# Omni-BASIC-BOTTOM.net
KiCad netlist of a schematic drawn in EAGLE
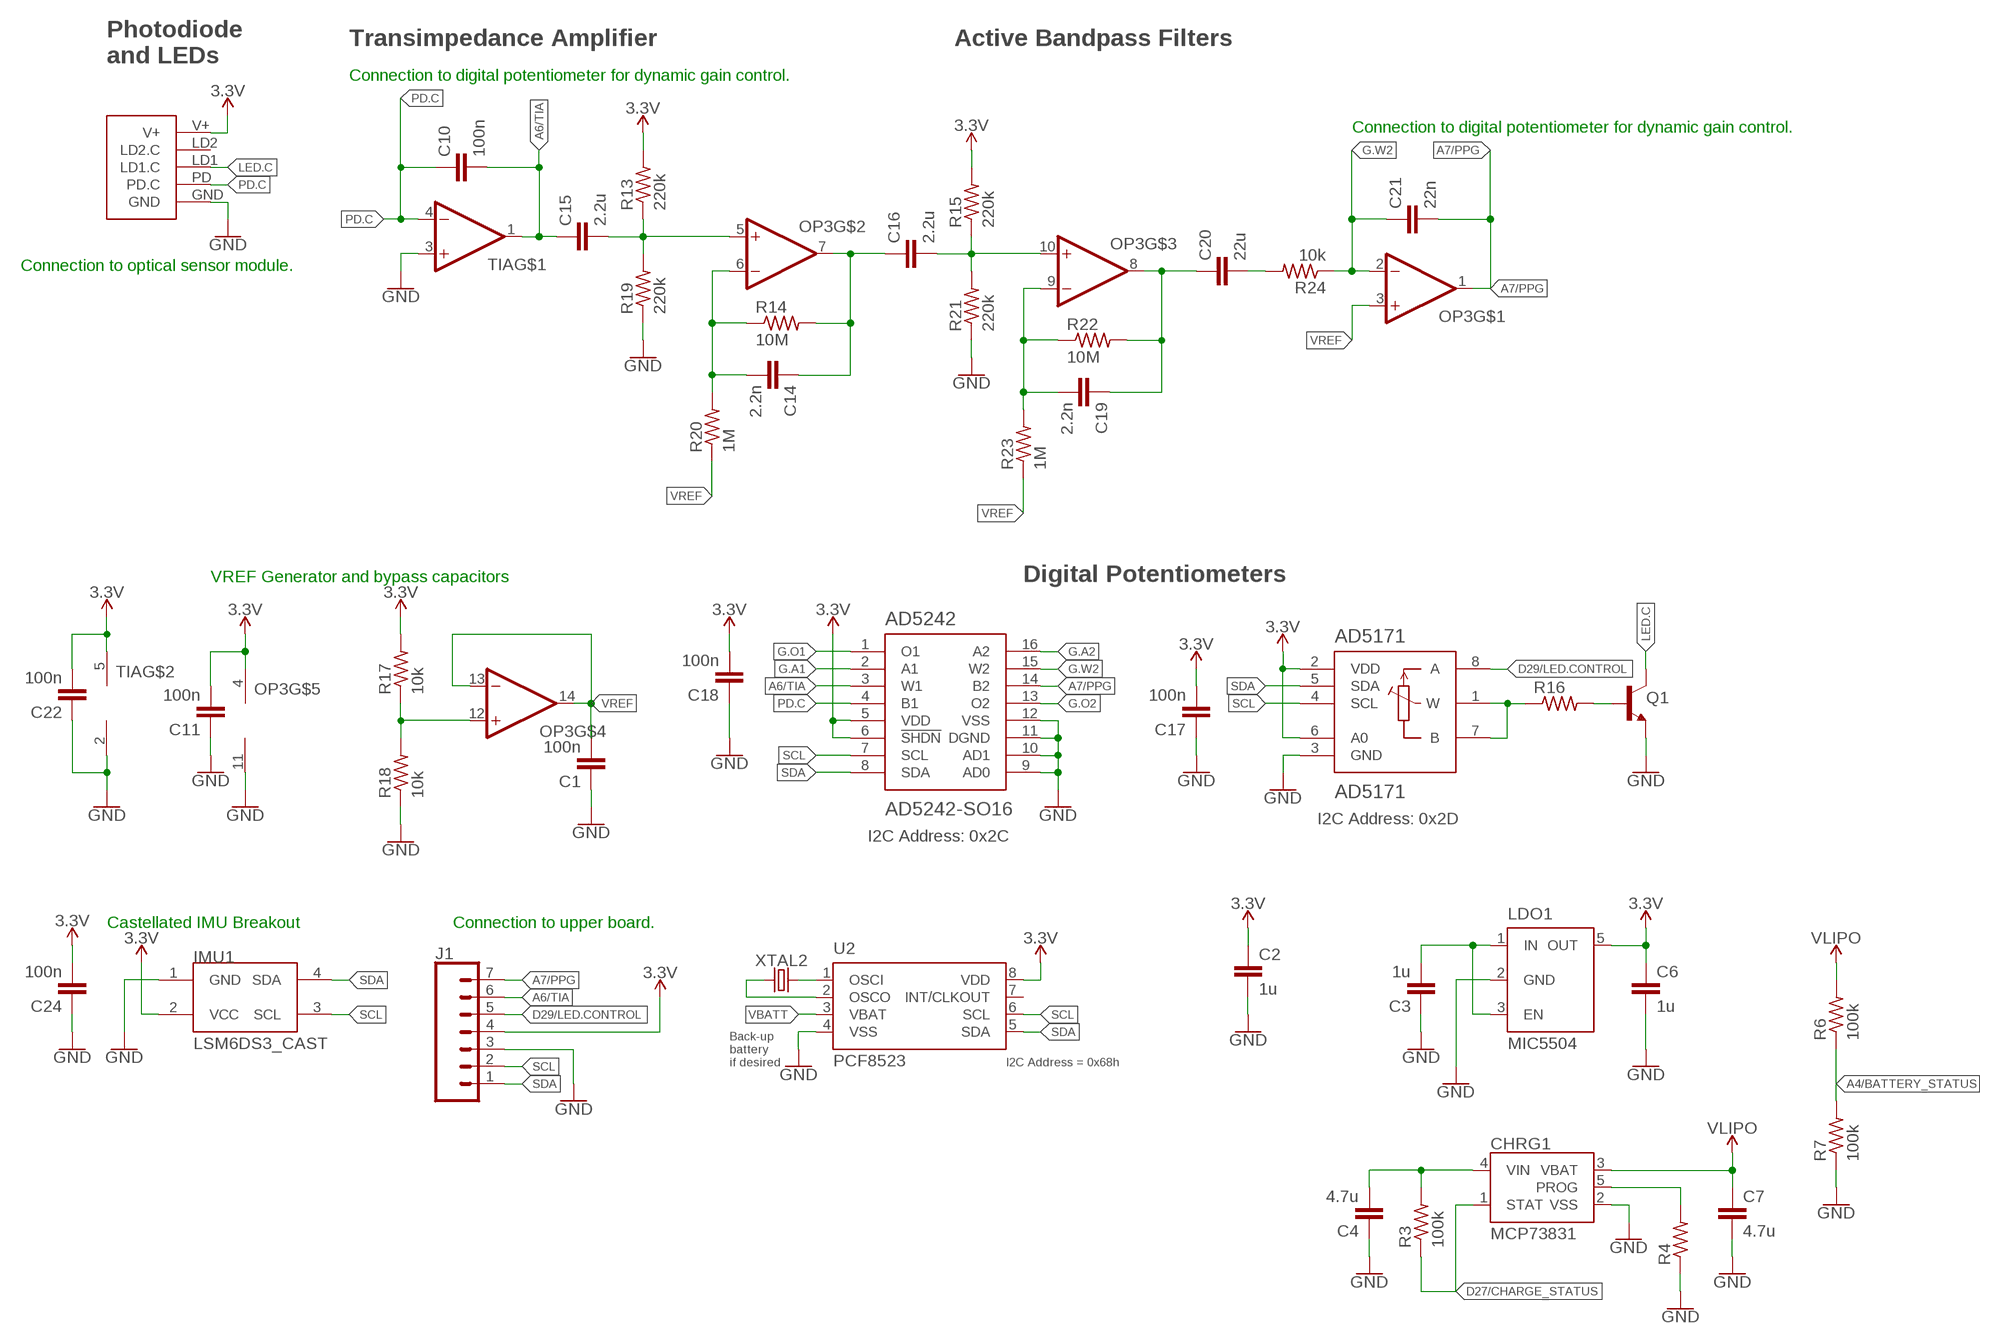
[diagram p0: schematic, sheet 1]

(export (version "E")
  (design (tool "Eeschema 10.0.6"))
  (components
    (comp (ref "AD5171")
      (value "AD5171")
      (footprint "eagle-import:SOT-23-8")
      (libsource (lib "eagle-import") (part "AD5171"))
    )
    (comp (ref "AD5242")
      (value "AD5242-SO16")
      (footprint "eagle-import:SO16")
      (libsource (lib "eagle-import") (part "AD5242-SO16"))
    )
    (comp (ref "C1")
      (value "100n")
      (footprint "eagle-import:C0603")
      (libsource (lib "eagle-import") (part "CAPACITOR0603"))
    )
    (comp (ref "C2")
      (value "1u")
      (footprint "eagle-import:C0603")
      (libsource (lib "eagle-import") (part "CAPACITOR0603"))
    )
    (comp (ref "C3")
      (value "1u")
      (footprint "eagle-import:C0603")
      (libsource (lib "eagle-import") (part "CAPACITOR0603"))
    )
    (comp (ref "C4")
      (value "4.7u")
      (footprint "eagle-import:C0603")
      (libsource (lib "eagle-import") (part "CAPACITOR0603"))
    )
    (comp (ref "C6")
      (value "1u")
      (footprint "eagle-import:C0603")
      (libsource (lib "eagle-import") (part "CAPACITOR0603"))
    )
    (comp (ref "C7")
      (value "4.7u")
      (footprint "eagle-import:C0603")
      (libsource (lib "eagle-import") (part "CAPACITOR0603"))
    )
    (comp (ref "C10")
      (value "100n")
      (footprint "eagle-import:C0603")
      (libsource (lib "eagle-import") (part "CAPACITOR0603"))
    )
    (comp (ref "C11")
      (value "100n")
      (footprint "eagle-import:C0603")
      (libsource (lib "eagle-import") (part "CAPACITOR0603"))
    )
    (comp (ref "C14")
      (value "2.2n")
      (footprint "eagle-import:C0603")
      (libsource (lib "eagle-import") (part "CAPACITOR0603"))
    )
    (comp (ref "C15")
      (value "2.2u")
      (footprint "eagle-import:C0603")
      (libsource (lib "eagle-import") (part "CAPACITOR0603"))
    )
    (comp (ref "C16")
      (value "2.2u")
      (footprint "eagle-import:C0603")
      (libsource (lib "eagle-import") (part "CAPACITOR0603"))
    )
    (comp (ref "C17")
      (value "100n")
      (footprint "eagle-import:C0603")
      (libsource (lib "eagle-import") (part "CAPACITOR0603"))
    )
    (comp (ref "C18")
      (value "100n")
      (footprint "eagle-import:C0603")
      (libsource (lib "eagle-import") (part "CAPACITOR0603"))
    )
    (comp (ref "C19")
      (value "2.2n")
      (footprint "eagle-import:C0603")
      (libsource (lib "eagle-import") (part "CAPACITOR0603"))
    )
    (comp (ref "C20")
      (value "22u")
      (footprint "eagle-import:C0603")
      (libsource (lib "eagle-import") (part "CAPACITOR0603"))
    )
    (comp (ref "C21")
      (value "22n")
      (footprint "eagle-import:C0603")
      (libsource (lib "eagle-import") (part "CAPACITOR0603"))
    )
    (comp (ref "C22")
      (value "100n")
      (footprint "eagle-import:C0603")
      (libsource (lib "eagle-import") (part "CAPACITOR0603"))
    )
    (comp (ref "C24")
      (value "100n")
      (footprint "eagle-import:C0603")
      (libsource (lib "eagle-import") (part "CAPACITOR0603"))
    )
    (comp (ref "CHRG1")
      (value "MCP73831")
      (footprint "eagle-import:SOT23-5")
      (libsource (lib "eagle-import") (part "MCP73831"))
    )
    (comp (ref "IMU1")
      (value "LSM6DS3_CAST")
      (footprint "eagle-import:LSM6DS3_CAST")
      (libsource (lib "eagle-import") (part "LSM6DS3_CAST"))
    )
    (comp (ref "J1")
      (value "CONN_07-1.27MM")
      (footprint "eagle-import:1X07_1.27MM")
      (libsource (lib "eagle-import") (part "CONN_07-1.27MM"))
    )
    (comp (ref "LDO1")
      (value "MIC5504")
      (footprint "eagle-import:SOT23-5")
      (libsource (lib "eagle-import") (part "MIC5504"))
    )
    (comp (ref "OP3")
      (value "OP-QUAD-SO14")
      (footprint "eagle-import:SO14")
      (libsource (lib "eagle-import") (part "OP-QUAD-SO14"))
    )
    (comp (ref "Q1")
      (value "NPN-GENERIC")
      (footprint "eagle-import:SOT23-3")
      (libsource (lib "eagle-import") (part "NPN-GENERIC"))
    )
    (comp (ref "R3")
      (value "100k")
      (footprint "eagle-import:R0603")
      (libsource (lib "eagle-import") (part "RESISTOR0603"))
    )
    (comp (ref "R4")
      (value "RESISTOR0603")
      (footprint "eagle-import:R0603")
      (libsource (lib "eagle-import") (part "RESISTOR0603"))
    )
    (comp (ref "R6")
      (value "100k")
      (footprint "eagle-import:R0603")
      (libsource (lib "eagle-import") (part "RESISTOR0603"))
    )
    (comp (ref "R7")
      (value "100k")
      (footprint "eagle-import:R0603")
      (libsource (lib "eagle-import") (part "RESISTOR0603"))
    )
    (comp (ref "R13")
      (value "220k")
      (footprint "eagle-import:R0603")
      (libsource (lib "eagle-import") (part "RESISTOR0603"))
    )
    (comp (ref "R14")
      (value "10M")
      (footprint "eagle-import:R0603")
      (libsource (lib "eagle-import") (part "RESISTOR0603"))
    )
    (comp (ref "R15")
      (value "220k")
      (footprint "eagle-import:R0603")
      (libsource (lib "eagle-import") (part "RESISTOR0603"))
    )
    (comp (ref "R16")
      (value "RESISTOR0603")
      (footprint "eagle-import:R0603")
      (libsource (lib "eagle-import") (part "RESISTOR0603"))
    )
    (comp (ref "R17")
      (value "10k")
      (footprint "eagle-import:R0402")
      (libsource (lib "eagle-import") (part "RESISTOR0402"))
    )
    (comp (ref "R18")
      (value "10k")
      (footprint "eagle-import:R0402")
      (libsource (lib "eagle-import") (part "RESISTOR0402"))
    )
    (comp (ref "R19")
      (value "220k")
      (footprint "eagle-import:R0603")
      (libsource (lib "eagle-import") (part "RESISTOR0603"))
    )
    (comp (ref "R20")
      (value "1M")
      (footprint "eagle-import:R0603")
      (libsource (lib "eagle-import") (part "RESISTOR0603"))
    )
    (comp (ref "R21")
      (value "220k")
      (footprint "eagle-import:R0603")
      (libsource (lib "eagle-import") (part "RESISTOR0603"))
    )
    (comp (ref "R22")
      (value "10M")
      (footprint "eagle-import:R0603")
      (libsource (lib "eagle-import") (part "RESISTOR0603"))
    )
    (comp (ref "R23")
      (value "1M")
      (footprint "eagle-import:R0603")
      (libsource (lib "eagle-import") (part "RESISTOR0603"))
    )
    (comp (ref "R24")
      (value "10k")
      (footprint "eagle-import:R0603")
      (libsource (lib "eagle-import") (part "RESISTOR0603"))
    )
    (comp (ref "TIA")
      (value "OP-SINGLEOT")
      (footprint "eagle-import:SOT23-5")
      (libsource (lib "eagle-import") (part "OP-SINGLEOT"))
    )
    (comp (ref "U$3")
      (value "PPG.MODULE.2")
      (footprint "eagle-import:PPG.MODULE.2")
      (libsource (lib "eagle-import") (part "PPG.MODULE.2"))
    )
    (comp (ref "U2")
      (value "PCF8523")
      (footprint "eagle-import:SO8")
      (libsource (lib "eagle-import") (part "PCF8523"))
    )
    (comp (ref "XTAL2")
      (value "32.7680kHz")
      (footprint "eagle-import:2-SMD.NOLEAD.2.0MMTO1.2MM")
      (fields (field (name "FREQ") "32.7680KHZ"))
      (libsource (lib "eagle-import") (part "CRYSTALECS-.327-12.5-12-C-TR"))
    )
  )
  (nets
    (net (code "1") (name "3.3V") (class "Default")
      (node (ref "AD5171") (pin "2") (pinfunction "VDD_2") (pintype "bidirectional"))
      (node (ref "AD5171") (pin "6") (pinfunction "A0_6") (pintype "bidirectional"))
      (node (ref "AD5242") (pin "5") (pinfunction "VDD_5") (pintype "bidirectional"))
      (node (ref "AD5242") (pin "6") (pinfunction "~{SHDN}_6") (pintype "bidirectional"))
      (node (ref "C11") (pin "2") (pinfunction "2_2") (pintype "passive"))
      (node (ref "C17") (pin "2") (pinfunction "2_2") (pintype "passive"))
      (node (ref "C18") (pin "2") (pinfunction "2_2") (pintype "passive"))
      (node (ref "C2") (pin "1") (pinfunction "1_1") (pintype "passive"))
      (node (ref "C22") (pin "2") (pinfunction "2_2") (pintype "passive"))
      (node (ref "C24") (pin "2") (pinfunction "2_2") (pintype "passive"))
      (node (ref "C6") (pin "1") (pinfunction "1_1") (pintype "passive"))
      (node (ref "IMU1") (pin "2") (pinfunction "VCC_2") (pintype "bidirectional"))
      (node (ref "J1") (pin "4") (pinfunction "4_4") (pintype "passive"))
      (node (ref "LDO1") (pin "5") (pinfunction "OUT_5") (pintype "bidirectional"))
      (node (ref "OP3") (pin "4") (pinfunction "V+_4") (pintype "power_in"))
      (node (ref "R13") (pin "2") (pinfunction "2_2") (pintype "passive"))
      (node (ref "R15") (pin "2") (pinfunction "2_2") (pintype "passive"))
      (node (ref "R17") (pin "2") (pinfunction "2_2") (pintype "passive"))
      (node (ref "TIA") (pin "5") (pinfunction "V+_5") (pintype "power_in"))
      (node (ref "U$3") (pin "V+") (pinfunction "V+_V+") (pintype "bidirectional"))
      (node (ref "U2") (pin "8") (pinfunction "VDD_8") (pintype "power_in"))
    )
    (net (code "2") (name "A4{slash}BATTERY_STATUS") (class "Default")
      (node (ref "R6") (pin "1") (pinfunction "1_1") (pintype "passive"))
      (node (ref "R7") (pin "2") (pinfunction "2_2") (pintype "passive"))
    )
    (net (code "3") (name "A6{slash}TIA") (class "Default")
      (node (ref "AD5242") (pin "3") (pinfunction "W1_3") (pintype "bidirectional"))
      (node (ref "C10") (pin "2") (pinfunction "2_2") (pintype "passive"))
      (node (ref "C15") (pin "1") (pinfunction "1_1") (pintype "passive"))
      (node (ref "J1") (pin "6") (pinfunction "6_6") (pintype "passive"))
      (node (ref "TIA") (pin "1") (pinfunction "OUT_1") (pintype "output"))
    )
    (net (code "4") (name "A7{slash}PPG") (class "Default")
      (node (ref "AD5242") (pin "14") (pinfunction "B2_14") (pintype "bidirectional"))
      (node (ref "C21") (pin "2") (pinfunction "2_2") (pintype "passive"))
      (node (ref "J1") (pin "7") (pinfunction "7_7") (pintype "passive"))
      (node (ref "OP3") (pin "1") (pinfunction "OUT_1") (pintype "output"))
    )
    (net (code "5") (name "D27{slash}CHARGE_STATUS") (class "Default")
      (node (ref "CHRG1") (pin "1") (pinfunction "STAT_1") (pintype "output"))
      (node (ref "R3") (pin "1") (pinfunction "1_1") (pintype "passive"))
    )
    (net (code "6") (name "D29{slash}LED.CONTROL") (class "Default")
      (node (ref "AD5171") (pin "8") (pinfunction "A_8") (pintype "bidirectional"))
      (node (ref "J1") (pin "5") (pinfunction "5_5") (pintype "passive"))
    )
    (net (code "7") (name "G.A1") (class "Default")
      (node (ref "AD5242") (pin "2") (pinfunction "A1_2") (pintype "bidirectional"))
    )
    (net (code "8") (name "G.A2") (class "Default")
      (node (ref "AD5242") (pin "16") (pinfunction "A2_16") (pintype "bidirectional"))
    )
    (net (code "9") (name "G.O1") (class "Default")
      (node (ref "AD5242") (pin "1") (pinfunction "O1_1") (pintype "bidirectional"))
    )
    (net (code "10") (name "G.O2") (class "Default")
      (node (ref "AD5242") (pin "13") (pinfunction "O2_13") (pintype "bidirectional"))
    )
    (net (code "11") (name "G.W2") (class "Default")
      (node (ref "AD5242") (pin "15") (pinfunction "W2_15") (pintype "bidirectional"))
      (node (ref "C21") (pin "1") (pinfunction "1_1") (pintype "passive"))
      (node (ref "OP3") (pin "2") (pinfunction "-IN_2") (pintype "input"))
      (node (ref "R24") (pin "1") (pinfunction "1_1") (pintype "passive"))
    )
    (net (code "12") (name "GND") (class "Default")
      (node (ref "AD5171") (pin "3") (pinfunction "GND_3") (pintype "bidirectional"))
      (node (ref "AD5242") (pin "10") (pinfunction "AD1_10") (pintype "bidirectional"))
      (node (ref "AD5242") (pin "11") (pinfunction "DGND_11") (pintype "bidirectional"))
      (node (ref "AD5242") (pin "12") (pinfunction "VSS_12") (pintype "bidirectional"))
      (node (ref "AD5242") (pin "9") (pinfunction "AD0_9") (pintype "bidirectional"))
      (node (ref "C1") (pin "1") (pinfunction "1_1") (pintype "passive"))
      (node (ref "C11") (pin "1") (pinfunction "1_1") (pintype "passive"))
      (node (ref "C17") (pin "1") (pinfunction "1_1") (pintype "passive"))
      (node (ref "C18") (pin "1") (pinfunction "1_1") (pintype "passive"))
      (node (ref "C2") (pin "2") (pinfunction "2_2") (pintype "passive"))
      (node (ref "C22") (pin "1") (pinfunction "1_1") (pintype "passive"))
      (node (ref "C24") (pin "1") (pinfunction "1_1") (pintype "passive"))
      (node (ref "C3") (pin "1") (pinfunction "1_1") (pintype "passive"))
      (node (ref "C4") (pin "1") (pinfunction "1_1") (pintype "passive"))
      (node (ref "C6") (pin "2") (pinfunction "2_2") (pintype "passive"))
      (node (ref "C7") (pin "2") (pinfunction "2_2") (pintype "passive"))
      (node (ref "CHRG1") (pin "2") (pinfunction "VSS_2") (pintype "power_in"))
      (node (ref "IMU1") (pin "1") (pinfunction "GND_1") (pintype "bidirectional"))
      (node (ref "J1") (pin "3") (pinfunction "3_3") (pintype "passive"))
      (node (ref "LDO1") (pin "2") (pinfunction "GND_2") (pintype "bidirectional"))
      (node (ref "OP3") (pin "11") (pinfunction "V-_11") (pintype "power_in"))
      (node (ref "Q1") (pin "2") (pinfunction "E_2") (pintype "passive"))
      (node (ref "R18") (pin "1") (pinfunction "1_1") (pintype "passive"))
      (node (ref "R19") (pin "1") (pinfunction "1_1") (pintype "passive"))
      (node (ref "R21") (pin "1") (pinfunction "1_1") (pintype "passive"))
      (node (ref "R4") (pin "1") (pinfunction "1_1") (pintype "passive"))
      (node (ref "R7") (pin "1") (pinfunction "1_1") (pintype "passive"))
      (node (ref "TIA") (pin "2") (pinfunction "V-_2") (pintype "power_in"))
      (node (ref "TIA") (pin "3") (pinfunction "+IN_3") (pintype "input"))
      (node (ref "U$3") (pin "GND") (pinfunction "GND_GND") (pintype "bidirectional"))
      (node (ref "U2") (pin "4") (pinfunction "VSS_4") (pintype "power_in"))
    )
    (net (code "13") (name "LED.C") (class "Default")
      (node (ref "Q1") (pin "3") (pinfunction "C_3") (pintype "passive"))
      (node (ref "U$3") (pin "LD1") (pinfunction "LD1.C_LD1") (pintype "bidirectional"))
    )
    (net (code "14") (name "Net-(AD5171-B)") (class "Default")
      (node (ref "AD5171") (pin "1") (pinfunction "W_1") (pintype "bidirectional"))
      (node (ref "AD5171") (pin "7") (pinfunction "B_7") (pintype "bidirectional"))
      (node (ref "R16") (pin "1") (pinfunction "1_1") (pintype "passive"))
    )
    (net (code "15") (name "Net-(C20-Pad2)") (class "Default")
      (node (ref "C20") (pin "2") (pinfunction "2_2") (pintype "passive"))
      (node (ref "R24") (pin "2") (pinfunction "2_2") (pintype "passive"))
    )
    (net (code "16") (name "Net-(CHRG1-PROG)") (class "Default")
      (node (ref "CHRG1") (pin "5") (pinfunction "PROG_5") (pintype "input"))
      (node (ref "R4") (pin "2") (pinfunction "2_2") (pintype "passive"))
    )
    (net (code "17") (name "Net-(CHRG1-VIN)") (class "Default")
      (node (ref "C4") (pin "2") (pinfunction "2_2") (pintype "passive"))
      (node (ref "CHRG1") (pin "4") (pinfunction "VIN_4") (pintype "power_in"))
      (node (ref "R3") (pin "2") (pinfunction "2_2") (pintype "passive"))
    )
    (net (code "18") (name "Net-(LDO1-EN)") (class "Default")
      (node (ref "C3") (pin "2") (pinfunction "2_2") (pintype "passive"))
      (node (ref "LDO1") (pin "1") (pinfunction "IN_1") (pintype "bidirectional"))
      (node (ref "LDO1") (pin "3") (pinfunction "EN_3") (pintype "bidirectional"))
    )
    (net (code "19") (name "Net-(OP3B-+IN)") (class "Default")
      (node (ref "C15") (pin "2") (pinfunction "2_2") (pintype "passive"))
      (node (ref "OP3") (pin "5") (pinfunction "+IN_5") (pintype "input"))
      (node (ref "R13") (pin "1") (pinfunction "1_1") (pintype "passive"))
      (node (ref "R19") (pin "2") (pinfunction "2_2") (pintype "passive"))
    )
    (net (code "20") (name "Net-(OP3B--IN)") (class "Default")
      (node (ref "C14") (pin "2") (pinfunction "2_2") (pintype "passive"))
      (node (ref "OP3") (pin "6") (pinfunction "-IN_6") (pintype "input"))
      (node (ref "R14") (pin "1") (pinfunction "1_1") (pintype "passive"))
      (node (ref "R20") (pin "2") (pinfunction "2_2") (pintype "passive"))
    )
    (net (code "21") (name "Net-(OP3B-OUT)") (class "Default")
      (node (ref "C14") (pin "1") (pinfunction "1_1") (pintype "passive"))
      (node (ref "C16") (pin "1") (pinfunction "1_1") (pintype "passive"))
      (node (ref "OP3") (pin "7") (pinfunction "OUT_7") (pintype "output"))
      (node (ref "R14") (pin "2") (pinfunction "2_2") (pintype "passive"))
    )
    (net (code "22") (name "Net-(OP3C-+IN)") (class "Default")
      (node (ref "C16") (pin "2") (pinfunction "2_2") (pintype "passive"))
      (node (ref "OP3") (pin "10") (pinfunction "+IN_10") (pintype "input"))
      (node (ref "R15") (pin "1") (pinfunction "1_1") (pintype "passive"))
      (node (ref "R21") (pin "2") (pinfunction "2_2") (pintype "passive"))
    )
    (net (code "23") (name "Net-(OP3C--IN)") (class "Default")
      (node (ref "C19") (pin "2") (pinfunction "2_2") (pintype "passive"))
      (node (ref "OP3") (pin "9") (pinfunction "-IN_9") (pintype "input"))
      (node (ref "R22") (pin "1") (pinfunction "1_1") (pintype "passive"))
      (node (ref "R23") (pin "2") (pinfunction "2_2") (pintype "passive"))
    )
    (net (code "24") (name "Net-(OP3C-OUT)") (class "Default")
      (node (ref "C19") (pin "1") (pinfunction "1_1") (pintype "passive"))
      (node (ref "C20") (pin "1") (pinfunction "1_1") (pintype "passive"))
      (node (ref "OP3") (pin "8") (pinfunction "OUT_8") (pintype "output"))
      (node (ref "R22") (pin "2") (pinfunction "2_2") (pintype "passive"))
    )
    (net (code "25") (name "Net-(OP3D-+IN)") (class "Default")
      (node (ref "OP3") (pin "12") (pinfunction "+IN_12") (pintype "input"))
      (node (ref "R17") (pin "1") (pinfunction "1_1") (pintype "passive"))
      (node (ref "R18") (pin "2") (pinfunction "2_2") (pintype "passive"))
    )
    (net (code "26") (name "Net-(Q1-B)") (class "Default")
      (node (ref "Q1") (pin "1") (pinfunction "B_1") (pintype "passive"))
      (node (ref "R16") (pin "2") (pinfunction "2_2") (pintype "passive"))
    )
    (net (code "27") (name "Net-(U2-OSCI)") (class "Default")
      (node (ref "U2") (pin "1") (pinfunction "OSCI_1") (pintype "bidirectional"))
      (node (ref "XTAL2") (pin "P$2") (pinfunction "2_P$2") (pintype "passive"))
    )
    (net (code "28") (name "Net-(U2-OSCO)") (class "Default")
      (node (ref "U2") (pin "2") (pinfunction "OSCO_2") (pintype "bidirectional"))
      (node (ref "XTAL2") (pin "P$1") (pinfunction "1_P$1") (pintype "passive"))
    )
    (net (code "29") (name "PD.C") (class "Default")
      (node (ref "AD5242") (pin "4") (pinfunction "B1_4") (pintype "bidirectional"))
      (node (ref "C10") (pin "1") (pinfunction "1_1") (pintype "passive"))
      (node (ref "TIA") (pin "4") (pinfunction "-IN_4") (pintype "input"))
      (node (ref "U$3") (pin "PD") (pinfunction "PD.C_PD") (pintype "bidirectional"))
    )
    (net (code "30") (name "SCL") (class "Default")
      (node (ref "AD5171") (pin "4") (pinfunction "SCL_4") (pintype "bidirectional"))
      (node (ref "AD5242") (pin "7") (pinfunction "SCL_7") (pintype "bidirectional"))
      (node (ref "IMU1") (pin "3") (pinfunction "SCL_3") (pintype "bidirectional"))
      (node (ref "J1") (pin "2") (pinfunction "2_2") (pintype "passive"))
      (node (ref "U2") (pin "6") (pinfunction "SCL_6") (pintype "bidirectional"))
    )
    (net (code "31") (name "SDA") (class "Default")
      (node (ref "AD5171") (pin "5") (pinfunction "SDA_5") (pintype "bidirectional"))
      (node (ref "AD5242") (pin "8") (pinfunction "SDA_8") (pintype "bidirectional"))
      (node (ref "IMU1") (pin "4") (pinfunction "SDA_4") (pintype "bidirectional"))
      (node (ref "J1") (pin "1") (pinfunction "1_1") (pintype "passive"))
      (node (ref "U2") (pin "5") (pinfunction "SDA_5") (pintype "bidirectional"))
    )
    (net (code "32") (name "VBATT") (class "Default")
      (node (ref "U2") (pin "3") (pinfunction "VBAT_3") (pintype "power_in"))
    )
    (net (code "33") (name "VLIPO") (class "Default")
      (node (ref "C7") (pin "1") (pinfunction "1_1") (pintype "passive"))
      (node (ref "CHRG1") (pin "3") (pinfunction "VBAT_3") (pintype "power_in"))
      (node (ref "R6") (pin "2") (pinfunction "2_2") (pintype "passive"))
    )
    (net (code "34") (name "VREF") (class "Default")
      (node (ref "C1") (pin "2") (pinfunction "2_2") (pintype "passive"))
      (node (ref "OP3") (pin "13") (pinfunction "-IN_13") (pintype "input"))
      (node (ref "OP3") (pin "14") (pinfunction "OUT_14") (pintype "output"))
      (node (ref "OP3") (pin "3") (pinfunction "+IN_3") (pintype "input"))
      (node (ref "R20") (pin "1") (pinfunction "1_1") (pintype "passive"))
      (node (ref "R23") (pin "1") (pinfunction "1_1") (pintype "passive"))
    )
    (net (code "35") (name "unconnected-(U$3-LD2.C-PadLD2)") (class "Default")
      (node (ref "U$3") (pin "LD2") (pinfunction "LD2.C_LD2") (pintype "bidirectional"))
    )
    (net (code "36") (name "unconnected-(U2-INT{slash}CLKOUT-Pad7)") (class "Default")
      (node (ref "U2") (pin "7") (pinfunction "INT/CLKOUT_7") (pintype "bidirectional"))
    )
  )
)
